# Led_Flasher.net
KiCad netlist of a schematic drawn in Altium Designer
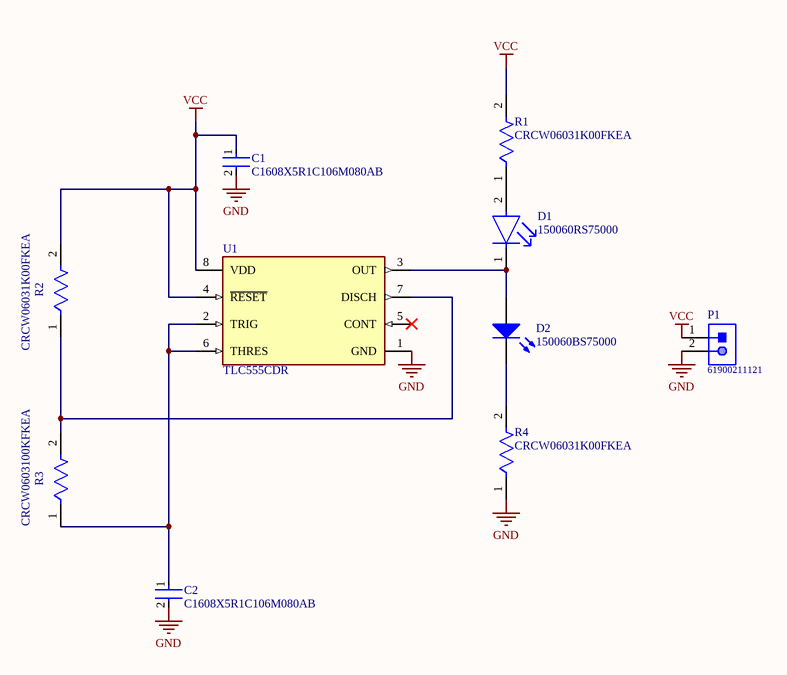
[diagram p0: Led_Flasher.SchDoc]

(export (version "E")
  (design (tool "Eeschema 10.0.6"))
  (components
    (comp (ref "C1")
      (value "C1608X5R1C106M080AB")
      (footprint "FP-C1608-MFG")
      (description "CAP CER 10UF 16V X5R 0603")
      (fields
        (field (name "OCTOPART") "https://octopart.com/c1608x5r1c106m080ab-tdk-26013480")
        (field (name "MANUFACTURER") "TDK Corporation")
      )
      (libsource (lib "Altium Content Vault") (part "11868f565c42a9108669ba33697ecf6"))
    )
    (comp (ref "C2")
      (value "C1608X5R1C106M080AB")
      (footprint "FP-C1608-MFG")
      (description "CAP CER 10UF 16V X5R 0603")
      (fields
        (field (name "OCTOPART") "https://octopart.com/c1608x5r1c106m080ab-tdk-26013480")
        (field (name "MANUFACTURER") "TDK Corporation")
      )
      (libsource (lib "Altium Content Vault") (part "11868f565c42a9108669ba33697ecf6"))
    )
    (comp (ref "D1")
      (value "150060RS75000")
      (footprint "FP-150060RS75000-MFG")
      (description "LED RED CLEAR 0603 SMD")
      (libsource (lib "Altium Content Vault") (part "8706943c75ba83719d021d2fdc84c58"))
    )
    (comp (ref "D2")
      (value "150060BS75000")
      (footprint "0603_A")
      (description "SMD mono-color Chip LED, WL-SMCW, Blue")
      (fields (field (name "MANUFACTURER") "Wuerth Elektronik"))
      (libsource (lib "Altium Content Vault") (part "WE-LED_K1A2-2"))
    )
    (comp (ref "P1")
      (value "61900211121")
      (footprint "61900211121")
      (description "Male Locking Header WR-WTB, THT, Vertical, pitch 2.54 mm, 1 x 2 position")
      (fields (field (name "MANUFACTURER") "Wurth Elektronik") (field (name "PUBLISHER") "WurthElektronik"))
      (libsource (lib "Altium Content Vault") (part "WE-CN-1P-M-R2"))
    )
    (comp (ref "R1")
      (value "CRCW06031K00FKEA")
      (footprint "FP-CRCW0603-e3-MFG")
      (description "RES Thick Film, 1kΩ, 1%, 0.1W, 100ppm/°C, 0603")
      (fields (field (name "TOLERANCE") "1%"))
      (libsource (lib "Altium Content Vault") (part "1029c3af85768c4190bb7ad29bc67b5"))
    )
    (comp (ref "R2")
      (value "CRCW06031K00FKEA")
      (footprint "FP-CRCW0603-e3-MFG")
      (description "RES Thick Film, 1kΩ, 1%, 0.1W, 100ppm/°C, 0603")
      (fields (field (name "TOLERANCE") "1%"))
      (libsource (lib "Altium Content Vault") (part "1029c3af85768c4190bb7ad29bc67b5"))
    )
    (comp (ref "R3")
      (value "CRCW0603100KFKEA")
      (footprint "FP-CRCW0603-e3-IPC_C")
      (description "RES Thick Film, 100kΩ, 1%, 0.1W, 100ppm/°C, 0603")
      (fields (field (name "TOLERANCE") "1%"))
      (libsource (lib "Altium Content Vault") (part "1029c3af85768c4190bb7ad29bc67b5"))
    )
    (comp (ref "R4")
      (value "CRCW06031K00FKEA")
      (footprint "FP-CRCW0603-e3-MFG")
      (description "RES Thick Film, 1kΩ, 1%, 0.1W, 100ppm/°C, 0603")
      (fields (field (name "TOLERANCE") "1%"))
      (libsource (lib "Altium Content Vault") (part "1029c3af85768c4190bb7ad29bc67b5"))
    )
    (comp (ref "U1")
      (value "TLC555CDR")
      (footprint "FP-D0008A-IPC_B")
      (description "IC OSC SGL TIMER 2.1MHZ 8-SOIC")
      (libsource (lib "Altium Content Vault") (part "fd1638d23bf5e420a54176ee4f8e783"))
    )
  )
  (nets
    (net (code "1") (name "GND") (class "Default")
      (node (ref "C1") (pin "2") (pinfunction "2_2") (pintype "passive"))
      (node (ref "C2") (pin "2") (pinfunction "2_2") (pintype "passive"))
      (node (ref "P1") (pin "2") (pinfunction "2_2") (pintype "passive"))
      (node (ref "R4") (pin "1") (pinfunction "1_1") (pintype "passive"))
      (node (ref "U1") (pin "1") (pinfunction "GND_1") (pintype "power_in"))
    )
    (net (code "2") (name "Net-(D1-A)") (class "Default")
      (node (ref "D1") (pin "2") (pinfunction "A_2") (pintype "passive"))
      (node (ref "R1") (pin "1") (pinfunction "1_1") (pintype "passive"))
    )
    (net (code "3") (name "Net-(D1-C)") (class "Default")
      (node (ref "D1") (pin "1") (pinfunction "C_1") (pintype "passive"))
      (node (ref "D2") (pin "2") (pinfunction "A_2") (pintype "passive"))
      (node (ref "U1") (pin "3") (pinfunction "OUT_3") (pintype "output"))
    )
    (net (code "4") (name "Net-(D2-K)") (class "Default")
      (node (ref "D2") (pin "1") (pinfunction "K_1") (pintype "passive"))
      (node (ref "R4") (pin "2") (pinfunction "2_2") (pintype "passive"))
    )
    (net (code "5") (name "Net-(U1-DISCH)") (class "Default")
      (node (ref "R2") (pin "1") (pinfunction "1_1") (pintype "passive"))
      (node (ref "R3") (pin "2") (pinfunction "2_2") (pintype "passive"))
      (node (ref "U1") (pin "7") (pinfunction "DISCH_7") (pintype "output"))
    )
    (net (code "6") (name "Net-(U1-THRES)") (class "Default")
      (node (ref "C2") (pin "1") (pinfunction "1_1") (pintype "passive"))
      (node (ref "R3") (pin "1") (pinfunction "1_1") (pintype "passive"))
      (node (ref "U1") (pin "2") (pinfunction "TRIG_2") (pintype "input"))
      (node (ref "U1") (pin "6") (pinfunction "THRES_6") (pintype "input"))
    )
    (net (code "7") (name "VCC") (class "Default")
      (node (ref "C1") (pin "1") (pinfunction "1_1") (pintype "passive"))
      (node (ref "P1") (pin "1") (pinfunction "1_1") (pintype "passive"))
      (node (ref "R1") (pin "2") (pinfunction "2_2") (pintype "passive"))
      (node (ref "R2") (pin "2") (pinfunction "2_2") (pintype "passive"))
      (node (ref "U1") (pin "4") (pinfunction "~{RESET}_4") (pintype "input"))
      (node (ref "U1") (pin "8") (pinfunction "VDD_8") (pintype "power_in"))
    )
    (net (code "8") (name "unconnected-(U1-CONT-Pad5)") (class "Default")
      (node (ref "U1") (pin "5") (pinfunction "CONT_5") (pintype "input+no_connect"))
    )
  )
)
